# scheme.net
KiCad netlist of a schematic drawn in EAGLE
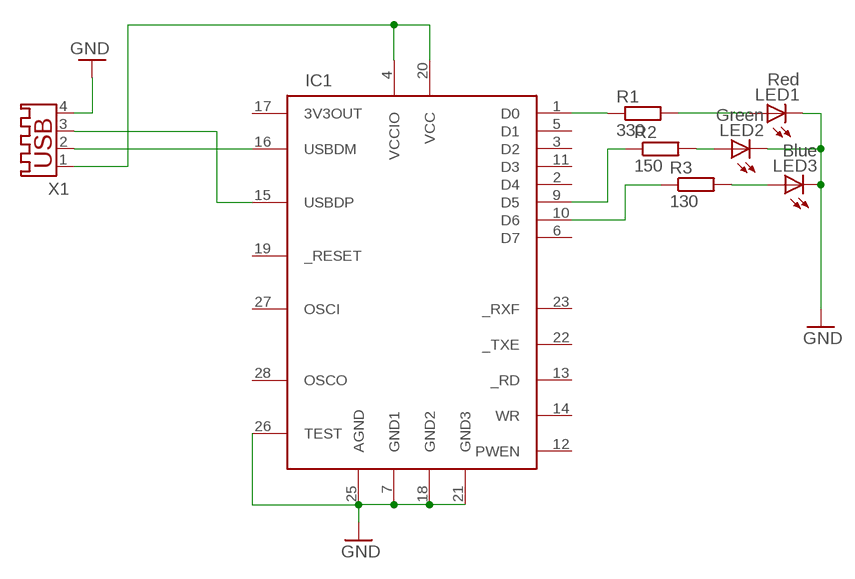
[diagram p0: schematic, sheet 1]

(export (version "E")
  (design (tool "Eeschema 10.0.6"))
  (components
    (comp (ref "IC1")
      (value "FT245RL")
      (footprint "eagle-import:SSOP28DB")
      (libsource (lib "eagle-import") (part "FT245RL"))
    )
    (comp (ref "LED1")
      (value "Red")
      (footprint "eagle-import:NFSG036BT")
      (libsource (lib "eagle-import") (part "NFSG036BT"))
    )
    (comp (ref "LED2")
      (value "Green")
      (footprint "eagle-import:NFSG036BT")
      (libsource (lib "eagle-import") (part "NFSG036BT"))
    )
    (comp (ref "LED3")
      (value "Blue")
      (footprint "eagle-import:NFSG036BT")
      (libsource (lib "eagle-import") (part "NFSG036BT"))
    )
    (comp (ref "R1")
      (value "330")
      (footprint "eagle-import:M1406")
      (libsource (lib "eagle-import") (part "R-EU_M1406"))
    )
    (comp (ref "R2")
      (value "150")
      (footprint "eagle-import:M1406")
      (libsource (lib "eagle-import") (part "R-EU_M1406"))
    )
    (comp (ref "R3")
      (value "130")
      (footprint "eagle-import:M1406")
      (libsource (lib "eagle-import") (part "R-EU_M1406"))
    )
    (comp (ref "X1")
      (value "USB-A003BOTTOM")
      (footprint "eagle-import:USB-A003-BOTTOM")
      (libsource (lib "eagle-import") (part "USB-A003BOTTOM"))
    )
  )
  (nets
    (net (code "1") (name "GND") (class "Default")
      (node (ref "IC1") (pin "18") (pinfunction "GND2_18") (pintype "power_in"))
      (node (ref "IC1") (pin "21") (pinfunction "GND3_21") (pintype "power_in"))
      (node (ref "IC1") (pin "25") (pinfunction "AGND_25") (pintype "power_in"))
      (node (ref "IC1") (pin "26") (pinfunction "TEST_26") (pintype "input"))
      (node (ref "IC1") (pin "7") (pinfunction "GND1_7") (pintype "power_in"))
      (node (ref "LED1") (pin "C") (pinfunction "C_C") (pintype "passive"))
      (node (ref "LED2") (pin "C") (pinfunction "C_C") (pintype "passive"))
      (node (ref "LED3") (pin "C") (pinfunction "C_C") (pintype "passive"))
      (node (ref "X1") (pin "4") (pinfunction "GND-4_4") (pintype "passive"))
    )
    (net (code "2") (name "Net-(IC1-D0)") (class "Default")
      (node (ref "IC1") (pin "1") (pinfunction "D0_1") (pintype "output"))
      (node (ref "R1") (pin "1") (pinfunction "1_1") (pintype "passive"))
    )
    (net (code "3") (name "Net-(IC1-D5)") (class "Default")
      (node (ref "IC1") (pin "9") (pinfunction "D5_9") (pintype "input"))
      (node (ref "R2") (pin "1") (pinfunction "1_1") (pintype "passive"))
    )
    (net (code "4") (name "Net-(IC1-D6)") (class "Default")
      (node (ref "IC1") (pin "10") (pinfunction "D6_10") (pintype "input"))
      (node (ref "R3") (pin "1") (pinfunction "1_1") (pintype "passive"))
    )
    (net (code "5") (name "Net-(IC1-USBDM)") (class "Default")
      (node (ref "IC1") (pin "16") (pinfunction "USBDM_16") (pintype "bidirectional"))
      (node (ref "X1") (pin "2") (pinfunction "D-2_2") (pintype "passive"))
    )
    (net (code "6") (name "Net-(IC1-USBDP)") (class "Default")
      (node (ref "IC1") (pin "15") (pinfunction "USBDP_15") (pintype "bidirectional"))
      (node (ref "X1") (pin "3") (pinfunction "D+3_3") (pintype "passive"))
    )
    (net (code "7") (name "Net-(IC1-VCC)") (class "Default")
      (node (ref "IC1") (pin "20") (pinfunction "VCC_20") (pintype "power_in"))
      (node (ref "IC1") (pin "4") (pinfunction "VCCIO_4") (pintype "power_in"))
      (node (ref "X1") (pin "1") (pinfunction "V+1_1") (pintype "passive"))
    )
    (net (code "8") (name "Net-(LED1-PadA)") (class "Default")
      (node (ref "LED1") (pin "A") (pinfunction "A_A") (pintype "passive"))
      (node (ref "R1") (pin "2") (pinfunction "2_2") (pintype "passive"))
    )
    (net (code "9") (name "Net-(LED2-PadA)") (class "Default")
      (node (ref "LED2") (pin "A") (pinfunction "A_A") (pintype "passive"))
      (node (ref "R2") (pin "2") (pinfunction "2_2") (pintype "passive"))
    )
    (net (code "10") (name "Net-(LED3-PadA)") (class "Default")
      (node (ref "LED3") (pin "A") (pinfunction "A_A") (pintype "passive"))
      (node (ref "R3") (pin "2") (pinfunction "2_2") (pintype "passive"))
    )
    (net (code "11") (name "unconnected-(IC1-3V3OUT-Pad17)") (class "Default")
      (node (ref "IC1") (pin "17") (pinfunction "3V3OUT_17") (pintype "output"))
    )
    (net (code "12") (name "unconnected-(IC1-D1-Pad5)") (class "Default")
      (node (ref "IC1") (pin "5") (pinfunction "D1_5") (pintype "input"))
    )
    (net (code "13") (name "unconnected-(IC1-D2-Pad3)") (class "Default")
      (node (ref "IC1") (pin "3") (pinfunction "D2_3") (pintype "output"))
    )
    (net (code "14") (name "unconnected-(IC1-D3-Pad11)") (class "Default")
      (node (ref "IC1") (pin "11") (pinfunction "D3_11") (pintype "input"))
    )
    (net (code "15") (name "unconnected-(IC1-D4-Pad2)") (class "Default")
      (node (ref "IC1") (pin "2") (pinfunction "D4_2") (pintype "output"))
    )
    (net (code "16") (name "unconnected-(IC1-D7-Pad6)") (class "Default")
      (node (ref "IC1") (pin "6") (pinfunction "D7_6") (pintype "input"))
    )
    (net (code "17") (name "unconnected-(IC1-OSCI-Pad27)") (class "Default")
      (node (ref "IC1") (pin "27") (pinfunction "OSCI_27") (pintype "input"))
    )
    (net (code "18") (name "unconnected-(IC1-OSCO-Pad28)") (class "Default")
      (node (ref "IC1") (pin "28") (pinfunction "OSCO_28") (pintype "output"))
    )
    (net (code "19") (name "unconnected-(IC1-PWEN-Pad12)") (class "Default")
      (node (ref "IC1") (pin "12") (pinfunction "PWEN_12") (pintype "bidirectional"))
    )
    (net (code "20") (name "unconnected-(IC1-WR-Pad14)") (class "Default")
      (node (ref "IC1") (pin "14") (pinfunction "WR_14") (pintype "bidirectional"))
    )
    (net (code "21") (name "unconnected-(IC1-_RD-Pad13)") (class "Default")
      (node (ref "IC1") (pin "13") (pinfunction "_RD_13") (pintype "bidirectional"))
    )
    (net (code "22") (name "unconnected-(IC1-_RESET-Pad19)") (class "Default")
      (node (ref "IC1") (pin "19") (pinfunction "_RESET_19") (pintype "input"))
    )
    (net (code "23") (name "unconnected-(IC1-_RXF-Pad23)") (class "Default")
      (node (ref "IC1") (pin "23") (pinfunction "_RXF_23") (pintype "bidirectional"))
    )
    (net (code "24") (name "unconnected-(IC1-_TXE-Pad22)") (class "Default")
      (node (ref "IC1") (pin "22") (pinfunction "_TXE_22") (pintype "bidirectional"))
    )
  )
)
